# Schematic.net
KiCad netlist of a schematic drawn in EAGLE
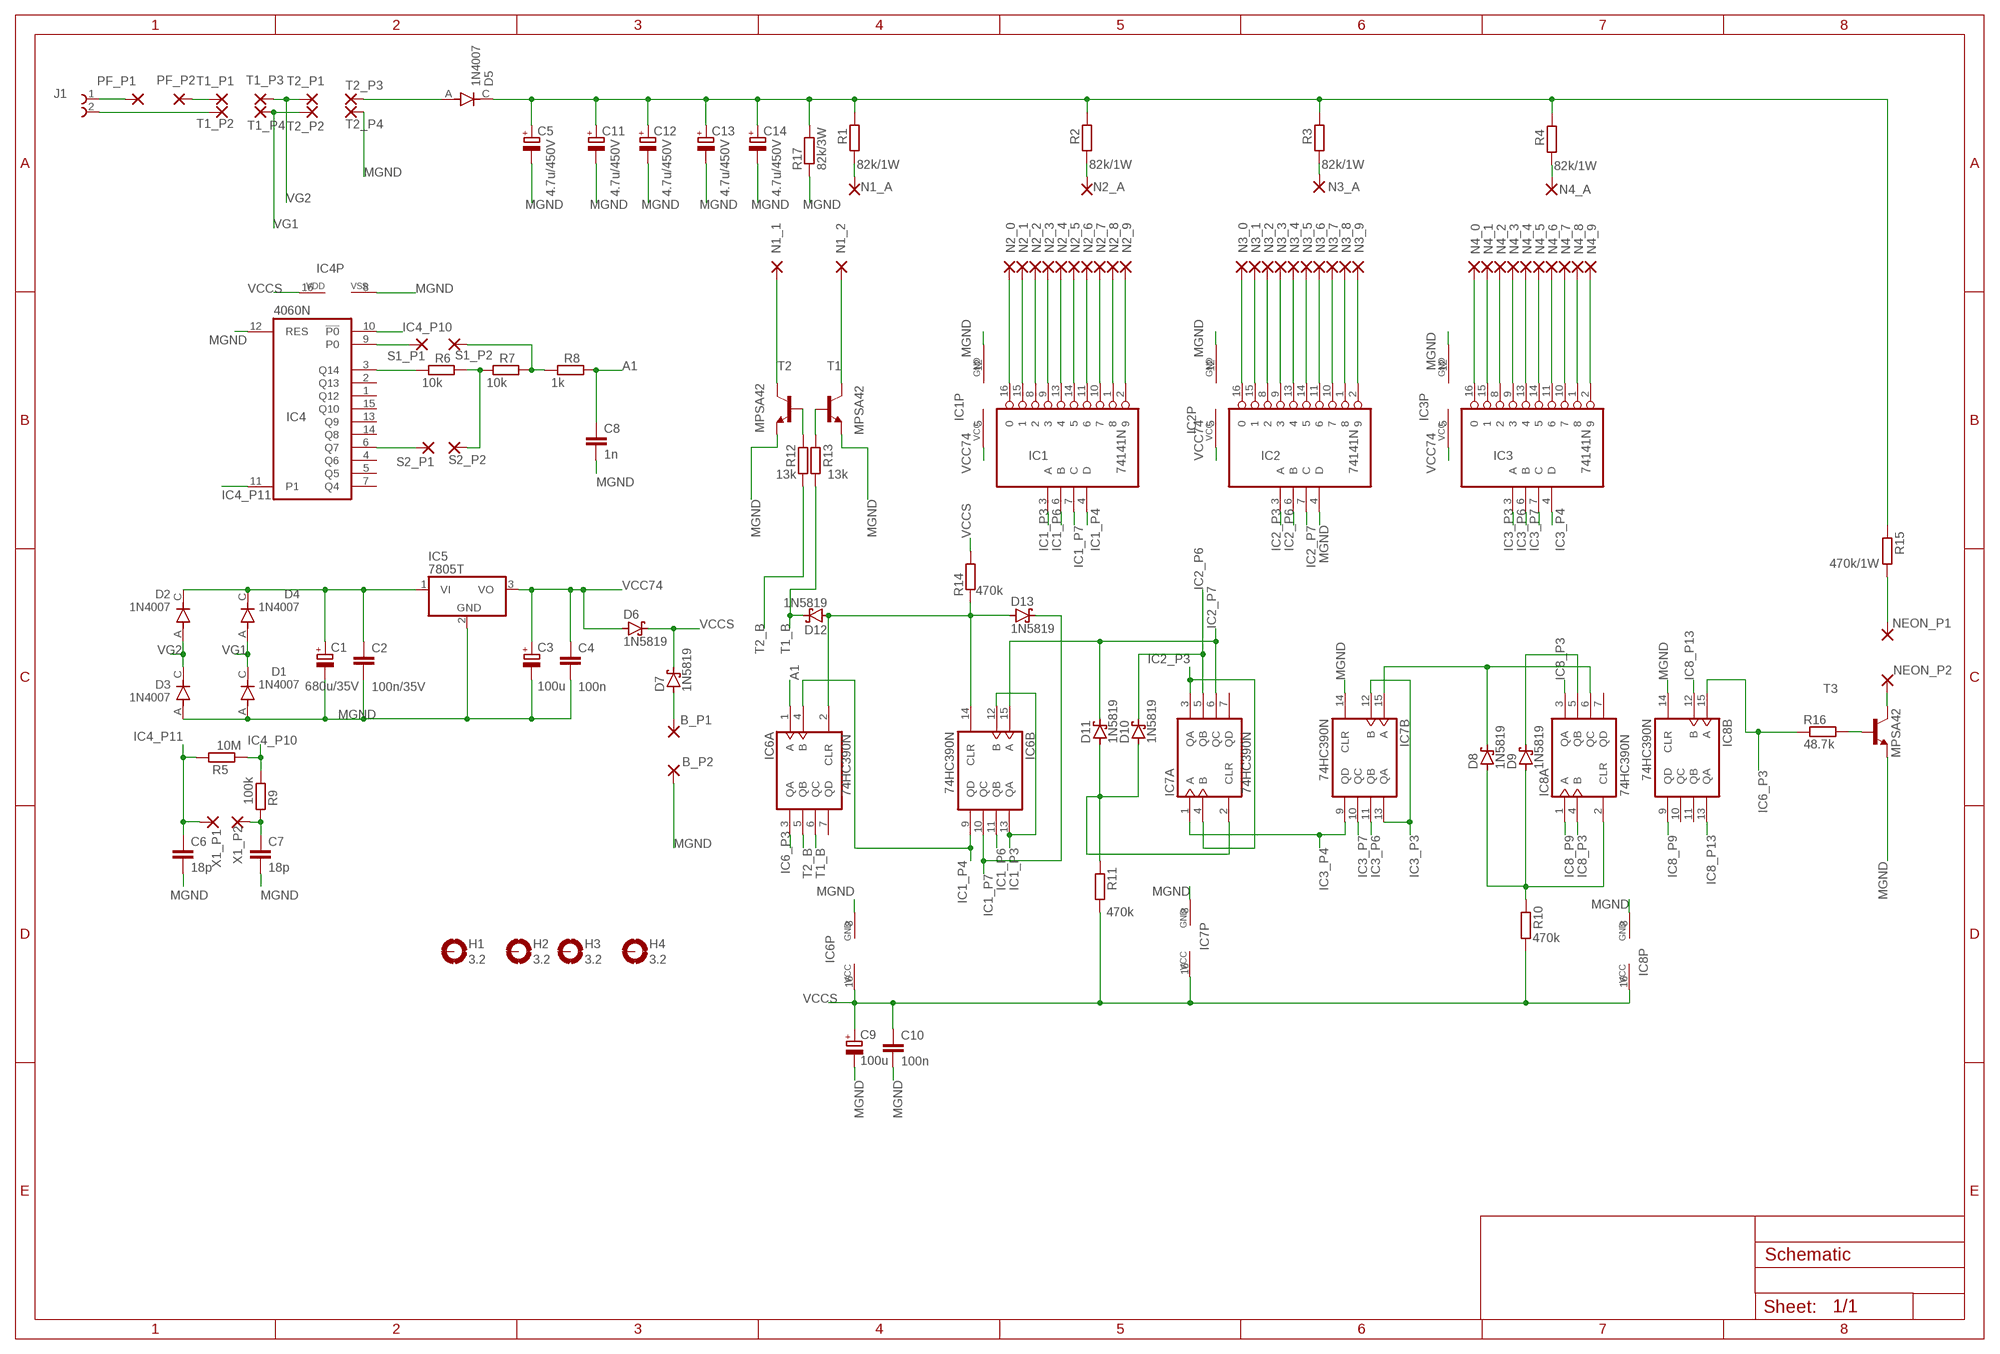
[diagram p0: schematic, sheet 1]

(export (version "E")
  (design (tool "Eeschema 10.0.6"))
  (components
    (comp (ref "B_P1")
      (value "3,81/1,4")
      (footprint "eagle-import:3,81_1,4")
      (libsource (lib "eagle-import") (part "3,81/1,4"))
    )
    (comp (ref "B_P2")
      (value "3,81/1,4")
      (footprint "eagle-import:3,81_1,4")
      (libsource (lib "eagle-import") (part "3,81/1,4"))
    )
    (comp (ref "C1")
      (value "680u/35V")
      (footprint "eagle-import:E5-10,5")
      (libsource (lib "eagle-import") (part "CPOL-EUE5-10.5"))
    )
    (comp (ref "C2")
      (value "100n/35V")
      (footprint "eagle-import:C025-024X044")
      (libsource (lib "eagle-import") (part "C-EU025-024X044"))
    )
    (comp (ref "C3")
      (value "100u")
      (footprint "eagle-import:E2-4")
      (libsource (lib "eagle-import") (part "CPOL-EUE2-4"))
    )
    (comp (ref "C4")
      (value "100n")
      (footprint "eagle-import:C025-024X044")
      (libsource (lib "eagle-import") (part "C-EU025-024X044"))
    )
    (comp (ref "C5")
      (value "4.7u/450V")
      (footprint "eagle-import:E5-8,5")
      (libsource (lib "eagle-import") (part "CPOL-EUE5-8.5"))
    )
    (comp (ref "C6")
      (value "18p")
      (footprint "eagle-import:C025-024X044")
      (libsource (lib "eagle-import") (part "C-EU025-024X044"))
    )
    (comp (ref "C7")
      (value "18p")
      (footprint "eagle-import:C025-024X044")
      (libsource (lib "eagle-import") (part "C-EU025-024X044"))
    )
    (comp (ref "C8")
      (value "1n")
      (footprint "eagle-import:C025-024X044")
      (libsource (lib "eagle-import") (part "C-EU025-024X044"))
    )
    (comp (ref "C9")
      (value "100u")
      (footprint "eagle-import:E2-4")
      (libsource (lib "eagle-import") (part "CPOL-EUE2-4"))
    )
    (comp (ref "C10")
      (value "100n")
      (footprint "eagle-import:C025-024X044")
      (libsource (lib "eagle-import") (part "C-EU025-024X044"))
    )
    (comp (ref "C11")
      (value "4.7u/450V")
      (footprint "eagle-import:E5-8,5")
      (libsource (lib "eagle-import") (part "CPOL-EUE5-8.5"))
    )
    (comp (ref "C12")
      (value "4.7u/450V")
      (footprint "eagle-import:E5-8,5")
      (libsource (lib "eagle-import") (part "CPOL-EUE5-8.5"))
    )
    (comp (ref "C13")
      (value "4.7u/450V")
      (footprint "eagle-import:E5-8,5")
      (libsource (lib "eagle-import") (part "CPOL-EUE5-8.5"))
    )
    (comp (ref "C14")
      (value "4.7u/450V")
      (footprint "eagle-import:E5-8,5")
      (libsource (lib "eagle-import") (part "CPOL-EUE5-8.5"))
    )
    (comp (ref "D1")
      (value "1N4007")
      (footprint "eagle-import:DIOAD1060W80L520D270")
      (fields (field (name "MF") "Diotec Semiconductor"))
      (libsource (lib "eagle-import") (part "1N4007"))
    )
    (comp (ref "D2")
      (value "1N4007")
      (footprint "eagle-import:DIOAD1060W80L520D270")
      (fields (field (name "MF") "Diotec Semiconductor"))
      (libsource (lib "eagle-import") (part "1N4007"))
    )
    (comp (ref "D3")
      (value "1N4007")
      (footprint "eagle-import:DIOAD1060W80L520D270")
      (fields (field (name "MF") "Diotec Semiconductor"))
      (libsource (lib "eagle-import") (part "1N4007"))
    )
    (comp (ref "D4")
      (value "1N4007")
      (footprint "eagle-import:DIOAD1060W80L520D270")
      (fields (field (name "MF") "Diotec Semiconductor"))
      (libsource (lib "eagle-import") (part "1N4007"))
    )
    (comp (ref "D5")
      (value "1N4007")
      (footprint "eagle-import:DIOAD1060W80L520D270")
      (fields (field (name "MF") "Diotec Semiconductor"))
      (libsource (lib "eagle-import") (part "1N4007"))
    )
    (comp (ref "D6")
      (value "1N5819")
      (footprint "eagle-import:DO41-7.6")
      (libsource (lib "eagle-import") (part "1N5819-B"))
    )
    (comp (ref "D7")
      (value "1N5819")
      (footprint "eagle-import:DO41-7.6")
      (libsource (lib "eagle-import") (part "1N5819-B"))
    )
    (comp (ref "D8")
      (value "1N5819")
      (footprint "eagle-import:DO41-7.6")
      (libsource (lib "eagle-import") (part "1N5819-B"))
    )
    (comp (ref "D9")
      (value "1N5819")
      (footprint "eagle-import:DO41-7.6")
      (libsource (lib "eagle-import") (part "1N5819-B"))
    )
    (comp (ref "D10")
      (value "1N5819")
      (footprint "eagle-import:DO41-7.6")
      (libsource (lib "eagle-import") (part "1N5819-B"))
    )
    (comp (ref "D11")
      (value "1N5819")
      (footprint "eagle-import:DO41-7.6")
      (libsource (lib "eagle-import") (part "1N5819-B"))
    )
    (comp (ref "D12")
      (value "1N5819")
      (footprint "eagle-import:DO41-7.6")
      (libsource (lib "eagle-import") (part "1N5819-B"))
    )
    (comp (ref "D13")
      (value "1N5819")
      (footprint "eagle-import:DO41-7.6")
      (libsource (lib "eagle-import") (part "1N5819-B"))
    )
    (comp (ref "H1")
      (value "3.2")
      (footprint "eagle-import:3,2-PAD")
      (libsource (lib "eagle-import") (part "MOUNT-PAD-ROUND3.2"))
    )
    (comp (ref "H2")
      (value "3.2")
      (footprint "eagle-import:3,2-PAD")
      (libsource (lib "eagle-import") (part "MOUNT-PAD-ROUND3.2"))
    )
    (comp (ref "H3")
      (value "3.2")
      (footprint "eagle-import:3,2-PAD")
      (libsource (lib "eagle-import") (part "MOUNT-PAD-ROUND3.2"))
    )
    (comp (ref "H4")
      (value "3.2")
      (footprint "eagle-import:3,2-PAD")
      (libsource (lib "eagle-import") (part "MOUNT-PAD-ROUND3.2"))
    )
    (comp (ref "IC1")
      (value "74141N")
      (footprint "eagle-import:DIL16")
      (libsource (lib "eagle-import") (part "74141N"))
    )
    (comp (ref "IC2")
      (value "74141N")
      (footprint "eagle-import:DIL16")
      (libsource (lib "eagle-import") (part "74141N"))
    )
    (comp (ref "IC3")
      (value "74141N")
      (footprint "eagle-import:DIL16")
      (libsource (lib "eagle-import") (part "74141N"))
    )
    (comp (ref "IC4")
      (value "4060N")
      (footprint "eagle-import:DIL16")
      (libsource (lib "eagle-import") (part "4060N"))
    )
    (comp (ref "IC5")
      (value "7805T")
      (footprint "eagle-import:TO220H")
      (libsource (lib "eagle-import") (part "78T05"))
    )
    (comp (ref "IC6")
      (value "74HC390N")
      (footprint "eagle-import:DIL16")
      (libsource (lib "eagle-import") (part "74390NHC"))
    )
    (comp (ref "IC7")
      (value "74HC390N")
      (footprint "eagle-import:DIL16")
      (libsource (lib "eagle-import") (part "74390NHC"))
    )
    (comp (ref "IC8")
      (value "74HC390N")
      (footprint "eagle-import:DIL16")
      (libsource (lib "eagle-import") (part "74390NHC"))
    )
    (comp (ref "J1")
      (value "691216910002")
      (footprint "eagle-import:691216910002")
      (fields (field (name "MF") "Wurth Electronics"))
      (libsource (lib "eagle-import") (part "691216910002"))
    )
    (comp (ref "N1_1")
      (value "3,81/1,4")
      (footprint "eagle-import:3,81_1,4")
      (libsource (lib "eagle-import") (part "3,81/1,4"))
    )
    (comp (ref "N1_2")
      (value "3,81/1,4")
      (footprint "eagle-import:3,81_1,4")
      (libsource (lib "eagle-import") (part "3,81/1,4"))
    )
    (comp (ref "N1_A")
      (value "3,81/1,4")
      (footprint "eagle-import:3,81_1,4")
      (libsource (lib "eagle-import") (part "3,81/1,4"))
    )
    (comp (ref "N2_0")
      (value "3,81/1,4")
      (footprint "eagle-import:3,81_1,4")
      (libsource (lib "eagle-import") (part "3,81/1,4"))
    )
    (comp (ref "N2_1")
      (value "3,81/1,4")
      (footprint "eagle-import:3,81_1,4")
      (libsource (lib "eagle-import") (part "3,81/1,4"))
    )
    (comp (ref "N2_2")
      (value "3,81/1,4")
      (footprint "eagle-import:3,81_1,4")
      (libsource (lib "eagle-import") (part "3,81/1,4"))
    )
    (comp (ref "N2_3")
      (value "3,81/1,4")
      (footprint "eagle-import:3,81_1,4")
      (libsource (lib "eagle-import") (part "3,81/1,4"))
    )
    (comp (ref "N2_4")
      (value "3,81/1,4")
      (footprint "eagle-import:3,81_1,4")
      (libsource (lib "eagle-import") (part "3,81/1,4"))
    )
    (comp (ref "N2_5")
      (value "3,81/1,4")
      (footprint "eagle-import:3,81_1,4")
      (libsource (lib "eagle-import") (part "3,81/1,4"))
    )
    (comp (ref "N2_6")
      (value "3,81/1,4")
      (footprint "eagle-import:3,81_1,4")
      (libsource (lib "eagle-import") (part "3,81/1,4"))
    )
    (comp (ref "N2_7")
      (value "3,81/1,4")
      (footprint "eagle-import:3,81_1,4")
      (libsource (lib "eagle-import") (part "3,81/1,4"))
    )
    (comp (ref "N2_8")
      (value "3,81/1,4")
      (footprint "eagle-import:3,81_1,4")
      (libsource (lib "eagle-import") (part "3,81/1,4"))
    )
    (comp (ref "N2_9")
      (value "3,81/1,4")
      (footprint "eagle-import:3,81_1,4")
      (libsource (lib "eagle-import") (part "3,81/1,4"))
    )
    (comp (ref "N2_A")
      (value "3,81/1,4")
      (footprint "eagle-import:3,81_1,4")
      (libsource (lib "eagle-import") (part "3,81/1,4"))
    )
    (comp (ref "N3_0")
      (value "3,81/1,4")
      (footprint "eagle-import:3,81_1,4")
      (libsource (lib "eagle-import") (part "3,81/1,4"))
    )
    (comp (ref "N3_1")
      (value "3,81/1,4")
      (footprint "eagle-import:3,81_1,4")
      (libsource (lib "eagle-import") (part "3,81/1,4"))
    )
    (comp (ref "N3_2")
      (value "3,81/1,4")
      (footprint "eagle-import:3,81_1,4")
      (libsource (lib "eagle-import") (part "3,81/1,4"))
    )
    (comp (ref "N3_3")
      (value "3,81/1,4")
      (footprint "eagle-import:3,81_1,4")
      (libsource (lib "eagle-import") (part "3,81/1,4"))
    )
    (comp (ref "N3_4")
      (value "3,81/1,4")
      (footprint "eagle-import:3,81_1,4")
      (libsource (lib "eagle-import") (part "3,81/1,4"))
    )
    (comp (ref "N3_5")
      (value "3,81/1,4")
      (footprint "eagle-import:3,81_1,4")
      (libsource (lib "eagle-import") (part "3,81/1,4"))
    )
    (comp (ref "N3_6")
      (value "3,81/1,4")
      (footprint "eagle-import:3,81_1,4")
      (libsource (lib "eagle-import") (part "3,81/1,4"))
    )
    (comp (ref "N3_7")
      (value "3,81/1,4")
      (footprint "eagle-import:3,81_1,4")
      (libsource (lib "eagle-import") (part "3,81/1,4"))
    )
    (comp (ref "N3_8")
      (value "3,81/1,4")
      (footprint "eagle-import:3,81_1,4")
      (libsource (lib "eagle-import") (part "3,81/1,4"))
    )
    (comp (ref "N3_9")
      (value "3,81/1,4")
      (footprint "eagle-import:3,81_1,4")
      (libsource (lib "eagle-import") (part "3,81/1,4"))
    )
    (comp (ref "N3_A")
      (value "3,81/1,4")
      (footprint "eagle-import:3,81_1,4")
      (libsource (lib "eagle-import") (part "3,81/1,4"))
    )
    (comp (ref "N4_0")
      (value "3,81/1,4")
      (footprint "eagle-import:3,81_1,4")
      (libsource (lib "eagle-import") (part "3,81/1,4"))
    )
    (comp (ref "N4_1")
      (value "3,81/1,4")
      (footprint "eagle-import:3,81_1,4")
      (libsource (lib "eagle-import") (part "3,81/1,4"))
    )
    (comp (ref "N4_2")
      (value "3,81/1,4")
      (footprint "eagle-import:3,81_1,4")
      (libsource (lib "eagle-import") (part "3,81/1,4"))
    )
    (comp (ref "N4_3")
      (value "3,81/1,4")
      (footprint "eagle-import:3,81_1,4")
      (libsource (lib "eagle-import") (part "3,81/1,4"))
    )
    (comp (ref "N4_4")
      (value "3,81/1,4")
      (footprint "eagle-import:3,81_1,4")
      (libsource (lib "eagle-import") (part "3,81/1,4"))
    )
    (comp (ref "N4_5")
      (value "3,81/1,4")
      (footprint "eagle-import:3,81_1,4")
      (libsource (lib "eagle-import") (part "3,81/1,4"))
    )
    (comp (ref "N4_6")
      (value "3,81/1,4")
      (footprint "eagle-import:3,81_1,4")
      (libsource (lib "eagle-import") (part "3,81/1,4"))
    )
    (comp (ref "N4_7")
      (value "3,81/1,4")
      (footprint "eagle-import:3,81_1,4")
      (libsource (lib "eagle-import") (part "3,81/1,4"))
    )
    (comp (ref "N4_8")
      (value "3,81/1,4")
      (footprint "eagle-import:3,81_1,4")
      (libsource (lib "eagle-import") (part "3,81/1,4"))
    )
    (comp (ref "N4_9")
      (value "3,81/1,4")
      (footprint "eagle-import:3,81_1,4")
      (libsource (lib "eagle-import") (part "3,81/1,4"))
    )
    (comp (ref "N4_A")
      (value "3,81/1,4")
      (footprint "eagle-import:3,81_1,4")
      (libsource (lib "eagle-import") (part "3,81/1,4"))
    )
    (comp (ref "NEON_P1")
      (value "3,81/1,4")
      (footprint "eagle-import:3,81_1,4")
      (libsource (lib "eagle-import") (part "3,81/1,4"))
    )
    (comp (ref "NEON_P2")
      (value "3,81/1,4")
      (footprint "eagle-import:3,81_1,4")
      (libsource (lib "eagle-import") (part "3,81/1,4"))
    )
    (comp (ref "PF_P1")
      (value "3,81/1,4")
      (footprint "eagle-import:3,81_1,4")
      (libsource (lib "eagle-import") (part "3,81/1,4"))
    )
    (comp (ref "PF_P2")
      (value "3,81/1,4")
      (footprint "eagle-import:3,81_1,4")
      (libsource (lib "eagle-import") (part "3,81/1,4"))
    )
    (comp (ref "R1")
      (value "82k/1W")
      (footprint "eagle-import:0207_10")
      (libsource (lib "eagle-import") (part "R-EU_0207/10"))
    )
    (comp (ref "R2")
      (value "82k/1W")
      (footprint "eagle-import:0207_10")
      (libsource (lib "eagle-import") (part "R-EU_0207/10"))
    )
    (comp (ref "R3")
      (value "82k/1W")
      (footprint "eagle-import:0207_10")
      (libsource (lib "eagle-import") (part "R-EU_0207/10"))
    )
    (comp (ref "R4")
      (value "82k/1W")
      (footprint "eagle-import:0207_10")
      (libsource (lib "eagle-import") (part "R-EU_0207/10"))
    )
    (comp (ref "R5")
      (value "10M")
      (footprint "eagle-import:0207_10")
      (libsource (lib "eagle-import") (part "R-EU_0207/10"))
    )
    (comp (ref "R6")
      (value "10k")
      (footprint "eagle-import:0207_10")
      (libsource (lib "eagle-import") (part "R-EU_0207/10"))
    )
    (comp (ref "R7")
      (value "10k")
      (footprint "eagle-import:0207_10")
      (libsource (lib "eagle-import") (part "R-EU_0207/10"))
    )
    (comp (ref "R8")
      (value "1k")
      (footprint "eagle-import:0207_10")
      (libsource (lib "eagle-import") (part "R-EU_0207/10"))
    )
    (comp (ref "R9")
      (value "100k")
      (footprint "eagle-import:0207_10")
      (libsource (lib "eagle-import") (part "R-EU_0207/10"))
    )
    (comp (ref "R10")
      (value "470k")
      (footprint "eagle-import:0207_10")
      (libsource (lib "eagle-import") (part "R-EU_0207/10"))
    )
    (comp (ref "R11")
      (value "470k")
      (footprint "eagle-import:0207_10")
      (libsource (lib "eagle-import") (part "R-EU_0207/10"))
    )
    (comp (ref "R12")
      (value "13k")
      (footprint "eagle-import:0207_10")
      (libsource (lib "eagle-import") (part "R-EU_0207/10"))
    )
    (comp (ref "R13")
      (value "13k")
      (footprint "eagle-import:0207_10")
      (libsource (lib "eagle-import") (part "R-EU_0207/10"))
    )
    (comp (ref "R14")
      (value "470k")
      (footprint "eagle-import:0207_10")
      (libsource (lib "eagle-import") (part "R-EU_0207/10"))
    )
    (comp (ref "R15")
      (value "470k/1W")
      (footprint "eagle-import:0207_10")
      (libsource (lib "eagle-import") (part "R-EU_0207/10"))
    )
    (comp (ref "R16")
      (value "48.7k")
      (footprint "eagle-import:0207_10")
      (libsource (lib "eagle-import") (part "R-EU_0207/10"))
    )
    (comp (ref "R17")
      (value "82k/3W")
      (footprint "eagle-import:0411_12")
      (libsource (lib "eagle-import") (part "R-EU_0411/12"))
    )
    (comp (ref "S1_P1")
      (value "3,81/1,4")
      (footprint "eagle-import:3,81_1,4")
      (libsource (lib "eagle-import") (part "3,81/1,4"))
    )
    (comp (ref "S1_P2")
      (value "3,81/1,4")
      (footprint "eagle-import:3,81_1,4")
      (libsource (lib "eagle-import") (part "3,81/1,4"))
    )
    (comp (ref "S2_P1")
      (value "3,81/1,4")
      (footprint "eagle-import:3,81_1,4")
      (libsource (lib "eagle-import") (part "3,81/1,4"))
    )
    (comp (ref "S2_P2")
      (value "3,81/1,4")
      (footprint "eagle-import:3,81_1,4")
      (libsource (lib "eagle-import") (part "3,81/1,4"))
    )
    (comp (ref "T1")
      (value "MPSA42")
      (footprint "eagle-import:TO92-EBC")
      (libsource (lib "eagle-import") (part "-NPN-TO92-EBCMPSA06"))
    )
    (comp (ref "T1_P1")
      (value "3,81/1,4")
      (footprint "eagle-import:3,81_1,4")
      (libsource (lib "eagle-import") (part "3,81/1,4"))
    )
    (comp (ref "T1_P2")
      (value "3,81/1,4")
      (footprint "eagle-import:3,81_1,4")
      (libsource (lib "eagle-import") (part "3,81/1,4"))
    )
    (comp (ref "T1_P3")
      (value "3,81/1,4")
      (footprint "eagle-import:3,81_1,4")
      (libsource (lib "eagle-import") (part "3,81/1,4"))
    )
    (comp (ref "T1_P4")
      (value "3,81/1,4")
      (footprint "eagle-import:3,81_1,4")
      (libsource (lib "eagle-import") (part "3,81/1,4"))
    )
    (comp (ref "T2")
      (value "MPSA42")
      (footprint "eagle-import:TO92-EBC")
      (libsource (lib "eagle-import") (part "-NPN-TO92-EBCMPSA06"))
    )
    (comp (ref "T2_P1")
      (value "3,81/1,4")
      (footprint "eagle-import:3,81_1,4")
      (libsource (lib "eagle-import") (part "3,81/1,4"))
    )
    (comp (ref "T2_P2")
      (value "3,81/1,4")
      (footprint "eagle-import:3,81_1,4")
      (libsource (lib "eagle-import") (part "3,81/1,4"))
    )
    (comp (ref "T2_P3")
      (value "3,81/1,4")
      (footprint "eagle-import:3,81_1,4")
      (libsource (lib "eagle-import") (part "3,81/1,4"))
    )
    (comp (ref "T2_P4")
      (value "3,81/1,4")
      (footprint "eagle-import:3,81_1,4")
      (libsource (lib "eagle-import") (part "3,81/1,4"))
    )
    (comp (ref "T3")
      (value "MPSA42")
      (footprint "eagle-import:TO92-EBC")
      (libsource (lib "eagle-import") (part "-NPN-TO92-EBCMPSA06"))
    )
    (comp (ref "X1_P1")
      (value "1,6/0,8")
      (footprint "eagle-import:1,6_0,8")
      (libsource (lib "eagle-import") (part "1,6/0,8"))
    )
    (comp (ref "X1_P2")
      (value "1,6/0,8")
      (footprint "eagle-import:1,6_0,8")
      (libsource (lib "eagle-import") (part "1,6/0,8"))
    )
  )
  (nets
    (net (code "1") (name "/A1") (class "Default")
      (node (ref "C8") (pin "1") (pinfunction "1_1") (pintype "passive"))
      (node (ref "IC6") (pin "1") (pinfunction "A_1") (pintype "input"))
      (node (ref "R8") (pin "2") (pinfunction "2_2") (pintype "passive"))
    )
    (net (code "2") (name "/IC1_P3") (class "Default")
      (node (ref "IC1") (pin "3") (pinfunction "A_3") (pintype "input"))
      (node (ref "IC6") (pin "12") (pinfunction "B_12") (pintype "input"))
      (node (ref "IC6") (pin "13") (pinfunction "QA_13") (pintype "output"))
    )
    (net (code "3") (name "/IC1_P4") (class "Default")
      (node (ref "IC1") (pin "4") (pinfunction "D_4") (pintype "input"))
      (node (ref "IC6") (pin "4") (pinfunction "B_4") (pintype "input"))
      (node (ref "IC6") (pin "9") (pinfunction "QD_9") (pintype "output"))
    )
    (net (code "4") (name "/IC1_P6") (class "Default")
      (node (ref "IC1") (pin "6") (pinfunction "B_6") (pintype "input"))
      (node (ref "IC6") (pin "11") (pinfunction "QB_11") (pintype "output"))
    )
    (net (code "5") (name "/IC1_P7") (class "Default")
      (node (ref "D13") (pin "C") (pinfunction "C_C") (pintype "passive"))
      (node (ref "IC1") (pin "7") (pinfunction "C_7") (pintype "input"))
      (node (ref "IC6") (pin "10") (pinfunction "QC_10") (pintype "output"))
    )
    (net (code "6") (name "/IC2_P3") (class "Default")
      (node (ref "IC2") (pin "3") (pinfunction "A_3") (pintype "input"))
      (node (ref "IC7") (pin "3") (pinfunction "QA_3") (pintype "output"))
      (node (ref "IC7") (pin "4") (pinfunction "B_4") (pintype "input"))
    )
    (net (code "7") (name "/IC2_P6") (class "Default")
      (node (ref "D10") (pin "C") (pinfunction "C_C") (pintype "passive"))
      (node (ref "IC2") (pin "6") (pinfunction "B_6") (pintype "input"))
      (node (ref "IC7") (pin "5") (pinfunction "QB_5") (pintype "output"))
    )
    (net (code "8") (name "/IC2_P7") (class "Default")
      (node (ref "D11") (pin "C") (pinfunction "C_C") (pintype "passive"))
      (node (ref "IC2") (pin "7") (pinfunction "C_7") (pintype "input"))
      (node (ref "IC6") (pin "15") (pinfunction "A_15") (pintype "input"))
      (node (ref "IC7") (pin "6") (pinfunction "QC_6") (pintype "output"))
    )
    (net (code "9") (name "/IC3_P3") (class "Default")
      (node (ref "IC3") (pin "3") (pinfunction "A_3") (pintype "input"))
      (node (ref "IC7") (pin "12") (pinfunction "B_12") (pintype "input"))
      (node (ref "IC7") (pin "13") (pinfunction "QA_13") (pintype "output"))
    )
    (net (code "10") (name "/IC3_P4") (class "Default")
      (node (ref "IC3") (pin "4") (pinfunction "D_4") (pintype "input"))
      (node (ref "IC7") (pin "1") (pinfunction "A_1") (pintype "input"))
      (node (ref "IC7") (pin "9") (pinfunction "QD_9") (pintype "output"))
    )
    (net (code "11") (name "/IC3_P6") (class "Default")
      (node (ref "IC3") (pin "6") (pinfunction "B_6") (pintype "input"))
      (node (ref "IC7") (pin "11") (pinfunction "QB_11") (pintype "output"))
    )
    (net (code "12") (name "/IC3_P7") (class "Default")
      (node (ref "IC3") (pin "7") (pinfunction "C_7") (pintype "input"))
      (node (ref "IC7") (pin "10") (pinfunction "QC_10") (pintype "output"))
    )
    (net (code "13") (name "/IC4_P10") (class "Default")
      (node (ref "IC4") (pin "10") (pinfunction "~{P0}_10") (pintype "output"))
      (node (ref "R5") (pin "1") (pinfunction "1_1") (pintype "passive"))
      (node (ref "R9") (pin "1") (pinfunction "1_1") (pintype "passive"))
    )
    (net (code "14") (name "/IC4_P11") (class "Default")
      (node (ref "C6") (pin "1") (pinfunction "1_1") (pintype "passive"))
      (node (ref "IC4") (pin "11") (pinfunction "P1_11") (pintype "input"))
      (node (ref "R5") (pin "2") (pinfunction "2_2") (pintype "passive"))
      (node (ref "X1_P1") (pin "1") (pinfunction "P_1") (pintype "passive"))
    )
    (net (code "15") (name "/IC6_P3") (class "Default")
      (node (ref "IC6") (pin "3") (pinfunction "QA_3") (pintype "output"))
      (node (ref "IC8") (pin "15") (pinfunction "A_15") (pintype "input"))
      (node (ref "R16") (pin "1") (pinfunction "1_1") (pintype "passive"))
    )
    (net (code "16") (name "/IC8_P3") (class "Default")
      (node (ref "IC8") (pin "3") (pinfunction "QA_3") (pintype "output"))
      (node (ref "IC8") (pin "4") (pinfunction "B_4") (pintype "input"))
    )
    (net (code "17") (name "/IC8_P9") (class "Default")
      (node (ref "IC8") (pin "1") (pinfunction "A_1") (pintype "input"))
      (node (ref "IC8") (pin "9") (pinfunction "QD_9") (pintype "output"))
    )
    (net (code "18") (name "/IC8_P13") (class "Default")
      (node (ref "IC8") (pin "12") (pinfunction "B_12") (pintype "input"))
      (node (ref "IC8") (pin "13") (pinfunction "QA_13") (pintype "output"))
    )
    (net (code "19") (name "/MGND") (class "Default")
      (node (ref "B_P2") (pin "1") (pinfunction "P_1") (pintype "passive"))
      (node (ref "C1") (pin "-") (pinfunction "-_-") (pintype "passive"))
      (node (ref "C10") (pin "2") (pinfunction "2_2") (pintype "passive"))
      (node (ref "C11") (pin "-") (pinfunction "-_-") (pintype "passive"))
      (node (ref "C12") (pin "-") (pinfunction "-_-") (pintype "passive"))
      (node (ref "C13") (pin "-") (pinfunction "-_-") (pintype "passive"))
      (node (ref "C14") (pin "-") (pinfunction "-_-") (pintype "passive"))
      (node (ref "C2") (pin "2") (pinfunction "2_2") (pintype "passive"))
      (node (ref "C3") (pin "-") (pinfunction "-_-") (pintype "passive"))
      (node (ref "C4") (pin "2") (pinfunction "2_2") (pintype "passive"))
      (node (ref "C5") (pin "-") (pinfunction "-_-") (pintype "passive"))
      (node (ref "C6") (pin "2") (pinfunction "2_2") (pintype "passive"))
      (node (ref "C7") (pin "2") (pinfunction "2_2") (pintype "passive"))
      (node (ref "C8") (pin "2") (pinfunction "2_2") (pintype "passive"))
      (node (ref "C9") (pin "-") (pinfunction "-_-") (pintype "passive"))
      (node (ref "D1") (pin "A") (pinfunction "A_A") (pintype "passive"))
      (node (ref "D3") (pin "A") (pinfunction "A_A") (pintype "passive"))
      (node (ref "IC1") (pin "12") (pinfunction "GND_12") (pintype "power_in"))
      (node (ref "IC2") (pin "12") (pinfunction "GND_12") (pintype "power_in"))
      (node (ref "IC2") (pin "4") (pinfunction "D_4") (pintype "input"))
      (node (ref "IC3") (pin "12") (pinfunction "GND_12") (pintype "power_in"))
      (node (ref "IC4") (pin "12") (pinfunction "RES_12") (pintype "input"))
      (node (ref "IC4") (pin "8") (pinfunction "VSS_8") (pintype "power_in"))
      (node (ref "IC5") (pin "2") (pinfunction "GND_2") (pintype "passive"))
      (node (ref "IC6") (pin "8") (pinfunction "GND_8") (pintype "power_in"))
      (node (ref "IC7") (pin "14") (pinfunction "CLR_14") (pintype "input"))
      (node (ref "IC7") (pin "8") (pinfunction "GND_8") (pintype "power_in"))
      (node (ref "IC8") (pin "14") (pinfunction "CLR_14") (pintype "input"))
      (node (ref "IC8") (pin "8") (pinfunction "GND_8") (pintype "power_in"))
      (node (ref "R17") (pin "1") (pinfunction "1_1") (pintype "passive"))
      (node (ref "T1") (pin "E") (pinfunction "E_E") (pintype "passive"))
      (node (ref "T2") (pin "E") (pinfunction "E_E") (pintype "passive"))
      (node (ref "T2_P4") (pin "1") (pinfunction "P_1") (pintype "passive"))
      (node (ref "T3") (pin "E") (pinfunction "E_E") (pintype "passive"))
    )
    (net (code "20") (name "/T1_B") (class "Default")
      (node (ref "D12") (pin "C") (pinfunction "C_C") (pintype "passive"))
      (node (ref "IC6") (pin "6") (pinfunction "QC_6") (pintype "output"))
      (node (ref "R13") (pin "1") (pinfunction "1_1") (pintype "passive"))
    )
    (net (code "21") (name "/T2_B") (class "Default")
      (node (ref "IC6") (pin "5") (pinfunction "QB_5") (pintype "output"))
      (node (ref "R12") (pin "1") (pinfunction "1_1") (pintype "passive"))
    )
    (net (code "22") (name "/VCC74") (class "Default")
      (node (ref "C3") (pin "+") (pinfunction "+_+") (pintype "passive"))
      (node (ref "C4") (pin "1") (pinfunction "1_1") (pintype "passive"))
      (node (ref "D6") (pin "A") (pinfunction "A_A") (pintype "passive"))
      (node (ref "IC1") (pin "5") (pinfunction "VCC_5") (pintype "power_in"))
      (node (ref "IC2") (pin "5") (pinfunction "VCC_5") (pintype "power_in"))
      (node (ref "IC3") (pin "5") (pinfunction "VCC_5") (pintype "power_in"))
      (node (ref "IC5") (pin "3") (pinfunction "VO_3") (pintype "passive"))
    )
    (net (code "23") (name "/VCCS") (class "Default")
      (node (ref "C10") (pin "1") (pinfunction "1_1") (pintype "passive"))
      (node (ref "C9") (pin "+") (pinfunction "+_+") (pintype "passive"))
      (node (ref "D6") (pin "C") (pinfunction "C_C") (pintype "passive"))
      (node (ref "D7") (pin "C") (pinfunction "C_C") (pintype "passive"))
      (node (ref "IC4") (pin "16") (pinfunction "VDD_16") (pintype "power_in"))
      (node (ref "IC6") (pin "16") (pinfunction "VCC_16") (pintype "power_in"))
      (node (ref "IC7") (pin "16") (pinfunction "VCC_16") (pintype "power_in"))
      (node (ref "IC8") (pin "16") (pinfunction "VCC_16") (pintype "power_in"))
      (node (ref "R10") (pin "2") (pinfunction "2_2") (pintype "passive"))
      (node (ref "R11") (pin "2") (pinfunction "2_2") (pintype "passive"))
      (node (ref "R14") (pin "2") (pinfunction "2_2") (pintype "passive"))
    )
    (net (code "24") (name "/VG1") (class "Default")
      (node (ref "D1") (pin "C") (pinfunction "C_C") (pintype "passive"))
      (node (ref "D4") (pin "A") (pinfunction "A_A") (pintype "passive"))
      (node (ref "T1_P4") (pin "1") (pinfunction "P_1") (pintype "passive"))
      (node (ref "T2_P2") (pin "1") (pinfunction "P_1") (pintype "passive"))
    )
    (net (code "25") (name "/VG2") (class "Default")
      (node (ref "D2") (pin "A") (pinfunction "A_A") (pintype "passive"))
      (node (ref "D3") (pin "C") (pinfunction "C_C") (pintype "passive"))
      (node (ref "T1_P3") (pin "1") (pinfunction "P_1") (pintype "passive"))
      (node (ref "T2_P1") (pin "1") (pinfunction "P_1") (pintype "passive"))
    )
    (net (code "26") (name "Net-(B_P1-P)") (class "Default")
      (node (ref "B_P1") (pin "1") (pinfunction "P_1") (pintype "passive"))
      (node (ref "D7") (pin "A") (pinfunction "A_A") (pintype "passive"))
    )
    (net (code "27") (name "Net-(C11-Pad+)") (class "Default")
      (node (ref "C11") (pin "+") (pinfunction "+_+") (pintype "passive"))
      (node (ref "C12") (pin "+") (pinfunction "+_+") (pintype "passive"))
      (node (ref "C13") (pin "+") (pinfunction "+_+") (pintype "passive"))
      (node (ref "C14") (pin "+") (pinfunction "+_+") (pintype "passive"))
      (node (ref "C5") (pin "+") (pinfunction "+_+") (pintype "passive"))
      (node (ref "D5") (pin "C") (pinfunction "C_C") (pintype "passive"))
      (node (ref "R1") (pin "2") (pinfunction "2_2") (pintype "passive"))
      (node (ref "R15") (pin "1") (pinfunction "1_1") (pintype "passive"))
      (node (ref "R17") (pin "2") (pinfunction "2_2") (pintype "passive"))
      (node (ref "R2") (pin "2") (pinfunction "2_2") (pintype "passive"))
      (node (ref "R3") (pin "2") (pinfunction "2_2") (pintype "passive"))
      (node (ref "R4") (pin "2") (pinfunction "2_2") (pintype "passive"))
    )
    (net (code "28") (name "Net-(IC1A-0)") (class "Default")
      (node (ref "IC1") (pin "16") (pinfunction "0_16") (pintype "open_collector"))
      (node (ref "N2_0") (pin "1") (pinfunction "P_1") (pintype "passive"))
    )
    (net (code "29") (name "Net-(IC1A-1)") (class "Default")
      (node (ref "IC1") (pin "15") (pinfunction "1_15") (pintype "open_collector"))
      (node (ref "N2_1") (pin "1") (pinfunction "P_1") (pintype "passive"))
    )
    (net (code "30") (name "Net-(IC1A-2)") (class "Default")
      (node (ref "IC1") (pin "8") (pinfunction "2_8") (pintype "open_collector"))
      (node (ref "N2_2") (pin "1") (pinfunction "P_1") (pintype "passive"))
    )
    (net (code "31") (name "Net-(IC1A-3)") (class "Default")
      (node (ref "IC1") (pin "9") (pinfunction "3_9") (pintype "open_collector"))
      (node (ref "N2_3") (pin "1") (pinfunction "P_1") (pintype "passive"))
    )
    (net (code "32") (name "Net-(IC1A-4)") (class "Default")
      (node (ref "IC1") (pin "13") (pinfunction "4_13") (pintype "open_collector"))
      (node (ref "N2_4") (pin "1") (pinfunction "P_1") (pintype "passive"))
    )
    (net (code "33") (name "Net-(IC1A-5)") (class "Default")
      (node (ref "IC1") (pin "14") (pinfunction "5_14") (pintype "open_collector"))
      (node (ref "N2_5") (pin "1") (pinfunction "P_1") (pintype "passive"))
    )
    (net (code "34") (name "Net-(IC1A-6)") (class "Default")
      (node (ref "IC1") (pin "11") (pinfunction "6_11") (pintype "open_collector"))
      (node (ref "N2_6") (pin "1") (pinfunction "P_1") (pintype "passive"))
    )
    (net (code "35") (name "Net-(IC1A-7)") (class "Default")
      (node (ref "IC1") (pin "10") (pinfunction "7_10") (pintype "open_collector"))
      (node (ref "N2_7") (pin "1") (pinfunction "P_1") (pintype "passive"))
    )
    (net (code "36") (name "Net-(IC1A-8)") (class "Default")
      (node (ref "IC1") (pin "1") (pinfunction "8_1") (pintype "open_collector"))
      (node (ref "N2_8") (pin "1") (pinfunction "P_1") (pintype "passive"))
    )
    (net (code "37") (name "Net-(IC1A-9)") (class "Default")
      (node (ref "IC1") (pin "2") (pinfunction "9_2") (pintype "open_collector"))
      (node (ref "N2_9") (pin "1") (pinfunction "P_1") (pintype "passive"))
    )
    (net (code "38") (name "Net-(IC2A-0)") (class "Default")
      (node (ref "IC2") (pin "16") (pinfunction "0_16") (pintype "open_collector"))
      (node (ref "N3_0") (pin "1") (pinfunction "P_1") (pintype "passive"))
    )
    (net (code "39") (name "Net-(IC2A-1)") (class "Default")
      (node (ref "IC2") (pin "15") (pinfunction "1_15") (pintype "open_collector"))
      (node (ref "N3_1") (pin "1") (pinfunction "P_1") (pintype "passive"))
    )
    (net (code "40") (name "Net-(IC2A-2)") (class "Default")
      (node (ref "IC2") (pin "8") (pinfunction "2_8") (pintype "open_collector"))
      (node (ref "N3_2") (pin "1") (pinfunction "P_1") (pintype "passive"))
    )
    (net (code "41") (name "Net-(IC2A-3)") (class "Default")
      (node (ref "IC2") (pin "9") (pinfunction "3_9") (pintype "open_collector"))
      (node (ref "N3_3") (pin "1") (pinfunction "P_1") (pintype "passive"))
    )
    (net (code "42") (name "Net-(IC2A-4)") (class "Default")
      (node (ref "IC2") (pin "13") (pinfunction "4_13") (pintype "open_collector"))
      (node (ref "N3_4") (pin "1") (pinfunction "P_1") (pintype "passive"))
    )
    (net (code "43") (name "Net-(IC2A-5)") (class "Default")
      (node (ref "IC2") (pin "14") (pinfunction "5_14") (pintype "open_collector"))
      (node (ref "N3_5") (pin "1") (pinfunction "P_1") (pintype "passive"))
    )
    (net (code "44") (name "Net-(IC2A-6)") (class "Default")
      (node (ref "IC2") (pin "11") (pinfunction "6_11") (pintype "open_collector"))
      (node (ref "N3_6") (pin "1") (pinfunction "P_1") (pintype "passive"))
    )
    (net (code "45") (name "Net-(IC2A-7)") (class "Default")
      (node (ref "IC2") (pin "10") (pinfunction "7_10") (pintype "open_collector"))
      (node (ref "N3_7") (pin "1") (pinfunction "P_1") (pintype "passive"))
    )
    (net (code "46") (name "Net-(IC2A-8)") (class "Default")
      (node (ref "IC2") (pin "1") (pinfunction "8_1") (pintype "open_collector"))
      (node (ref "N3_8") (pin "1") (pinfunction "P_1") (pintype "passive"))
    )
    (net (code "47") (name "Net-(IC2A-9)") (class "Default")
      (node (ref "IC2") (pin "2") (pinfunction "9_2") (pintype "open_collector"))
      (node (ref "N3_9") (pin "1") (pinfunction "P_1") (pintype "passive"))
    )
    (net (code "48") (name "Net-(IC3A-0)") (class "Default")
      (node (ref "IC3") (pin "16") (pinfunction "0_16") (pintype "open_collector"))
      (node (ref "N4_0") (pin "1") (pinfunction "P_1") (pintype "passive"))
    )
    (net (code "49") (name "Net-(IC3A-1)") (class "Default")
      (node (ref "IC3") (pin "15") (pinfunction "1_15") (pintype "open_collector"))
      (node (ref "N4_1") (pin "1") (pinfunction "P_1") (pintype "passive"))
    )
    (net (code "50") (name "Net-(IC3A-2)") (class "Default")
      (node (ref "IC3") (pin "8") (pinfunction "2_8") (pintype "open_collector"))
      (node (ref "N4_2") (pin "1") (pinfunction "P_1") (pintype "passive"))
    )
    (net (code "51") (name "Net-(IC3A-3)") (class "Default")
      (node (ref "IC3") (pin "9") (pinfunction "3_9") (pintype "open_collector"))
      (node (ref "N4_3") (pin "1") (pinfunction "P_1") (pintype "passive"))
    )
    (net (code "52") (name "Net-(IC3A-4)") (class "Default")
      (node (ref "IC3") (pin "13") (pinfunction "4_13") (pintype "open_collector"))
      (node (ref "N4_4") (pin "1") (pinfunction "P_1") (pintype "passive"))
    )
    (net (code "53") (name "Net-(IC3A-5)") (class "Default")
      (node (ref "IC3") (pin "14") (pinfunction "5_14") (pintype "open_collector"))
      (node (ref "N4_5") (pin "1") (pinfunction "P_1") (pintype "passive"))
    )
    (net (code "54") (name "Net-(IC3A-6)") (class "Default")
      (node (ref "IC3") (pin "11") (pinfunction "6_11") (pintype "open_collector"))
      (node (ref "N4_6") (pin "1") (pinfunction "P_1") (pintype "passive"))
    )
    (net (code "55") (name "Net-(IC3A-7)") (class "Default")
      (node (ref "IC3") (pin "10") (pinfunction "7_10") (pintype "open_collector"))
      (node (ref "N4_7") (pin "1") (pinfunction "P_1") (pintype "passive"))
    )
    (net (code "56") (name "Net-(IC3A-8)") (class "Default")
      (node (ref "IC3") (pin "1") (pinfunction "8_1") (pintype "open_collector"))
      (node (ref "N4_8") (pin "1") (pinfunction "P_1") (pintype "passive"))
    )
    (net (code "57") (name "Net-(IC3A-9)") (class "Default")
      (node (ref "IC3") (pin "2") (pinfunction "9_2") (pintype "open_collector"))
      (node (ref "N4_9") (pin "1") (pinfunction "P_1") (pintype "passive"))
    )
    (net (code "58") (name "Net-(IC4A-P0)") (class "Default")
      (node (ref "IC4") (pin "9") (pinfunction "P0_9") (pintype "output"))
      (node (ref "S1_P1") (pin "1") (pinfunction "P_1") (pintype "passive"))
    )
    (net (code "59") (name "Net-(IC4A-Q7)") (class "Default")
      (node (ref "IC4") (pin "6") (pinfunction "Q7_6") (pintype "output"))
      (node (ref "S2_P1") (pin "1") (pinfunction "P_1") (pintype "passive"))
    )
    (net (code "60") (name "Net-(IC4A-Q14)") (class "Default")
      (node (ref "IC4") (pin "3") (pinfunction "Q14_3") (pintype "output"))
      (node (ref "R6") (pin "1") (pinfunction "1_1") (pintype "passive"))
    )
    (net (code "61") (name "Net-(IC5-VI)") (class "Default")
      (node (ref "C1") (pin "+") (pinfunction "+_+") (pintype "passive"))
      (node (ref "C2") (pin "1") (pinfunction "1_1") (pintype "passive"))
      (node (ref "D2") (pin "C") (pinfunction "C_C") (pintype "passive"))
      (node (ref "D4") (pin "C") (pinfunction "C_C") (pintype "passive"))
      (node (ref "IC5") (pin "1") (pinfunction "VI_1") (pintype "input"))
    )
    (net (code "62") (name "Net-(IC6A-CLR)") (class "Default")
      (node (ref "D12") (pin "A") (pinfunction "A_A") (pintype "passive"))
      (node (ref "D13") (pin "A") (pinfunction "A_A") (pintype "passive"))
      (node (ref "IC6") (pin "14") (pinfunction "CLR_14") (pintype "input"))
      (node (ref "IC6") (pin "2") (pinfunction "CLR_2") (pintype "input"))
      (node (ref "R14") (pin "1") (pinfunction "1_1") (pintype "passive"))
    )
    (net (code "63") (name "Net-(IC7A-CLR)") (class "Default")
      (node (ref "D10") (pin "A") (pinfunction "A_A") (pintype "passive"))
      (node (ref "D11") (pin "A") (pinfunction "A_A") (pintype "passive"))
      (node (ref "IC7") (pin "2") (pinfunction "CLR_2") (pintype "input"))
      (node (ref "R11") (pin "1") (pinfunction "1_1") (pintype "passive"))
    )
    (net (code "64") (name "Net-(IC7B-A)") (class "Default")
      (node (ref "D8") (pin "C") (pinfunction "C_C") (pintype "passive"))
      (node (ref "IC7") (pin "15") (pinfunction "A_15") (pintype "input"))
      (node (ref "IC8") (pin "6") (pinfunction "QC_6") (pintype "output"))
    )
    (net (code "65") (name "Net-(IC8A-CLR)") (class "Default")
      (node (ref "D8") (pin "A") (pinfunction "A_A") (pintype "passive"))
      (node (ref "D9") (pin "A") (pinfunction "A_A") (pintype "passive"))
      (node (ref "IC8") (pin "2") (pinfunction "CLR_2") (pintype "input"))
      (node (ref "R10") (pin "1") (pinfunction "1_1") (pintype "passive"))
    )
    (net (code "66") (name "Net-(IC8A-QB)") (class "Default")
      (node (ref "D9") (pin "C") (pinfunction "C_C") (pintype "passive"))
      (node (ref "IC8") (pin "5") (pinfunction "QB_5") (pintype "output"))
    )
    (net (code "67") (name "Net-(N1_1-P)") (class "Default")
      (node (ref "N1_1") (pin "1") (pinfunction "P_1") (pintype "passive"))
      (node (ref "T1") (pin "C") (pinfunction "C_C") (pintype "passive"))
    )
    (net (code "68") (name "Net-(N1_2-P)") (class "Default")
      (node (ref "N1_2") (pin "1") (pinfunction "P_1") (pintype "passive"))
      (node (ref "T2") (pin "C") (pinfunction "C_C") (pintype "passive"))
    )
    (net (code "69") (name "Net-(N1_A-P)") (class "Default")
      (node (ref "N1_A") (pin "1") (pinfunction "P_1") (pintype "passive"))
      (node (ref "R1") (pin "1") (pinfunction "1_1") (pintype "passive"))
    )
    (net (code "70") (name "Net-(N2_A-P)") (class "Default")
      (node (ref "N2_A") (pin "1") (pinfunction "P_1") (pintype "passive"))
      (node (ref "R2") (pin "1") (pinfunction "1_1") (pintype "passive"))
    )
    (net (code "71") (name "Net-(N3_A-P)") (class "Default")
      (node (ref "N3_A") (pin "1") (pinfunction "P_1") (pintype "passive"))
      (node (ref "R3") (pin "1") (pinfunction "1_1") (pintype "passive"))
    )
    (net (code "72") (name "Net-(N4_A-P)") (class "Default")
      (node (ref "N4_A") (pin "1") (pinfunction "P_1") (pintype "passive"))
      (node (ref "R4") (pin "1") (pinfunction "1_1") (pintype "passive"))
    )
    (net (code "73") (name "Net-(NEON_P1-P)") (class "Default")
      (node (ref "NEON_P1") (pin "1") (pinfunction "P_1") (pintype "passive"))
      (node (ref "R15") (pin "2") (pinfunction "2_2") (pintype "passive"))
    )
    (net (code "74") (name "Net-(NEON_P2-P)") (class "Default")
      (node (ref "NEON_P2") (pin "1") (pinfunction "P_1") (pintype "passive"))
      (node (ref "T3") (pin "C") (pinfunction "C_C") (pintype "passive"))
    )
    (net (code "75") (name "Net-(PF_P1-P)") (class "Default")
      (node (ref "J1") (pin "1") (pinfunction "1_1") (pintype "passive"))
      (node (ref "PF_P1") (pin "1") (pinfunction "P_1") (pintype "passive"))
    )
    (net (code "76") (name "Net-(PF_P2-P)") (class "Default")
      (node (ref "PF_P2") (pin "1") (pinfunction "P_1") (pintype "passive"))
      (node (ref "T1_P1") (pin "1") (pinfunction "P_1") (pintype "passive"))
    )
    (net (code "77") (name "Net-(R12-Pad2)") (class "Default")
      (node (ref "R12") (pin "2") (pinfunction "2_2") (pintype "passive"))
      (node (ref "T1") (pin "B") (pinfunction "B_B") (pintype "passive"))
    )
    (net (code "78") (name "Net-(R13-Pad2)") (class "Default")
      (node (ref "R13") (pin "2") (pinfunction "2_2") (pintype "passive"))
      (node (ref "T2") (pin "B") (pinfunction "B_B") (pintype "passive"))
    )
    (net (code "79") (name "Net-(R16-Pad2)") (class "Default")
      (node (ref "R16") (pin "2") (pinfunction "2_2") (pintype "passive"))
      (node (ref "T3") (pin "B") (pinfunction "B_B") (pintype "passive"))
    )
    (net (code "80") (name "Net-(S1_P2-P)") (class "Default")
      (node (ref "R7") (pin "2") (pinfunction "2_2") (pintype "passive"))
      (node (ref "R8") (pin "1") (pinfunction "1_1") (pintype "passive"))
      (node (ref "S1_P2") (pin "1") (pinfunction "P_1") (pintype "passive"))
    )
    (net (code "81") (name "Net-(S2_P2-P)") (class "Default")
      (node (ref "R6") (pin "2") (pinfunction "2_2") (pintype "passive"))
      (node (ref "R7") (pin "1") (pinfunction "1_1") (pintype "passive"))
      (node (ref "S2_P2") (pin "1") (pinfunction "P_1") (pintype "passive"))
    )
    (net (code "82") (name "Net-(T1_P2-P)") (class "Default")
      (node (ref "J1") (pin "2") (pinfunction "2_2") (pintype "passive"))
      (node (ref "T1_P2") (pin "1") (pinfunction "P_1") (pintype "passive"))
    )
    (net (code "83") (name "Net-(T2_P3-P)") (class "Default")
      (node (ref "D5") (pin "A") (pinfunction "A_A") (pintype "passive"))
      (node (ref "T2_P3") (pin "1") (pinfunction "P_1") (pintype "passive"))
    )
    (net (code "84") (name "Net-(X1_P2-P)") (class "Default")
      (node (ref "C7") (pin "1") (pinfunction "1_1") (pintype "passive"))
      (node (ref "R9") (pin "2") (pinfunction "2_2") (pintype "passive"))
      (node (ref "X1_P2") (pin "1") (pinfunction "P_1") (pintype "passive"))
    )
    (net (code "85") (name "unconnected-(H1-MOUNT-PadB3,2)") (class "Default")
      (node (ref "H1") (pin "B3,2") (pinfunction "MOUNT_B3,2") (pintype "passive"))
    )
    (net (code "86") (name "unconnected-(H2-MOUNT-PadB3,2)") (class "Default")
      (node (ref "H2") (pin "B3,2") (pinfunction "MOUNT_B3,2") (pintype "passive"))
    )
    (net (code "87") (name "unconnected-(H3-MOUNT-PadB3,2)") (class "Default")
      (node (ref "H3") (pin "B3,2") (pinfunction "MOUNT_B3,2") (pintype "passive"))
    )
    (net (code "88") (name "unconnected-(H4-MOUNT-PadB3,2)") (class "Default")
      (node (ref "H4") (pin "B3,2") (pinfunction "MOUNT_B3,2") (pintype "passive"))
    )
    (net (code "89") (name "unconnected-(IC4A-Q4-Pad7)") (class "Default")
      (node (ref "IC4") (pin "7") (pinfunction "Q4_7") (pintype "output"))
    )
    (net (code "90") (name "unconnected-(IC4A-Q5-Pad5)") (class "Default")
      (node (ref "IC4") (pin "5") (pinfunction "Q5_5") (pintype "output"))
    )
    (net (code "91") (name "unconnected-(IC4A-Q6-Pad4)") (class "Default")
      (node (ref "IC4") (pin "4") (pinfunction "Q6_4") (pintype "output"))
    )
    (net (code "92") (name "unconnected-(IC4A-Q8-Pad14)") (class "Default")
      (node (ref "IC4") (pin "14") (pinfunction "Q8_14") (pintype "output"))
    )
    (net (code "93") (name "unconnected-(IC4A-Q9-Pad13)") (class "Default")
      (node (ref "IC4") (pin "13") (pinfunction "Q9_13") (pintype "output"))
    )
    (net (code "94") (name "unconnected-(IC4A-Q10-Pad15)") (class "Default")
      (node (ref "IC4") (pin "15") (pinfunction "Q10_15") (pintype "output"))
    )
    (net (code "95") (name "unconnected-(IC4A-Q12-Pad1)") (class "Default")
      (node (ref "IC4") (pin "1") (pinfunction "Q12_1") (pintype "output"))
    )
    (net (code "96") (name "unconnected-(IC4A-Q13-Pad2)") (class "Default")
      (node (ref "IC4") (pin "2") (pinfunction "Q13_2") (pintype "output"))
    )
    (net (code "97") (name "unconnected-(IC6A-QD-Pad7)") (class "Default")
      (node (ref "IC6") (pin "7") (pinfunction "QD_7") (pintype "output"))
    )
    (net (code "98") (name "unconnected-(IC7A-QD-Pad7)") (class "Default")
      (node (ref "IC7") (pin "7") (pinfunction "QD_7") (pintype "output"))
    )
    (net (code "99") (name "unconnected-(IC8A-QD-Pad7)") (class "Default")
      (node (ref "IC8") (pin "7") (pinfunction "QD_7") (pintype "output"))
    )
    (net (code "100") (name "unconnected-(IC8B-QB-Pad11)") (class "Default")
      (node (ref "IC8") (pin "11") (pinfunction "QB_11") (pintype "output"))
    )
    (net (code "101") (name "unconnected-(IC8B-QC-Pad10)") (class "Default")
      (node (ref "IC8") (pin "10") (pinfunction "QC_10") (pintype "output"))
    )
  )
)
